# DarkPill_V1_1_eagle_V7_6.net
KiCad netlist of a schematic drawn in EAGLE
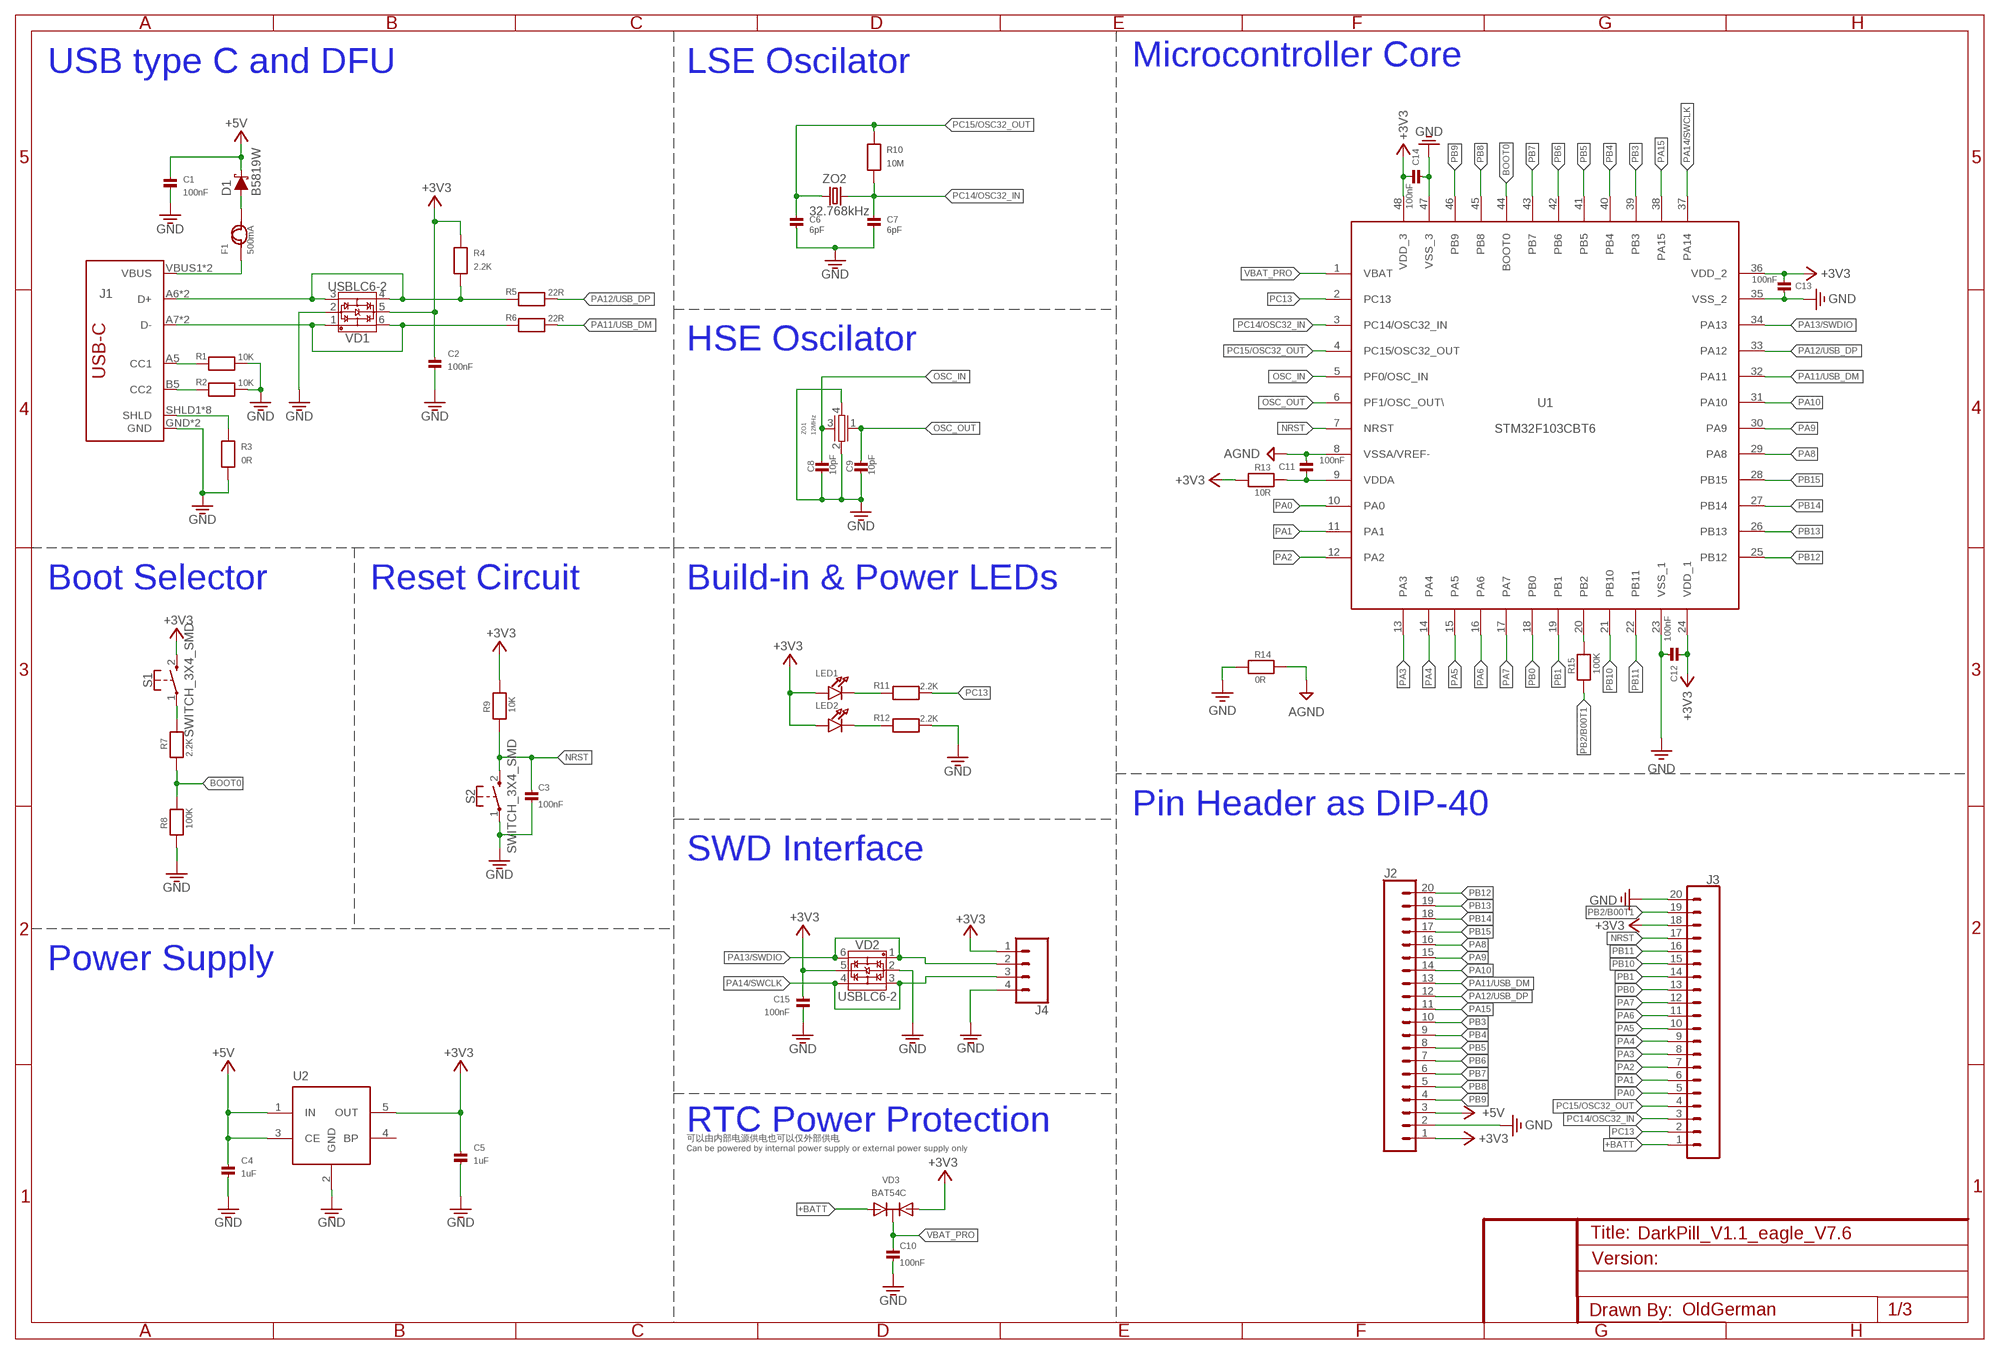
[diagram p0: schematic, sheet 1]

(export (version "E")
  (design (tool "Eeschema 10.0.6"))
  (components
    (comp (ref "C1")
      (value "100nF")
      (footprint "eagle-import:0603")
      (libsource (lib "eagle-import") (part "CAP_CERAMIC0603"))
    )
    (comp (ref "C2")
      (value "100nF")
      (footprint "eagle-import:0603")
      (libsource (lib "eagle-import") (part "CAP_CERAMIC0603"))
    )
    (comp (ref "C3")
      (value "100nF")
      (footprint "eagle-import:0603")
      (libsource (lib "eagle-import") (part "CAP_CERAMIC0603"))
    )
    (comp (ref "C4")
      (value "1uF")
      (footprint "eagle-import:0603")
      (libsource (lib "eagle-import") (part "CAP_CERAMIC0603"))
    )
    (comp (ref "C5")
      (value "1uF")
      (footprint "eagle-import:0603")
      (libsource (lib "eagle-import") (part "CAP_CERAMIC0603"))
    )
    (comp (ref "C6")
      (value "6pF")
      (footprint "eagle-import:0603")
      (libsource (lib "eagle-import") (part "CAP_CERAMIC0603"))
    )
    (comp (ref "C7")
      (value "6pF")
      (footprint "eagle-import:0603")
      (libsource (lib "eagle-import") (part "CAP_CERAMIC0603"))
    )
    (comp (ref "C8")
      (value "10pF")
      (footprint "eagle-import:0603")
      (libsource (lib "eagle-import") (part "CAP_CERAMIC0603"))
    )
    (comp (ref "C9")
      (value "10pF")
      (footprint "eagle-import:0603")
      (libsource (lib "eagle-import") (part "CAP_CERAMIC0603"))
    )
    (comp (ref "C10")
      (value "100nF")
      (footprint "eagle-import:0603")
      (libsource (lib "eagle-import") (part "CAP_CERAMIC0603"))
    )
    (comp (ref "C11")
      (value "100nF")
      (footprint "eagle-import:0603")
      (libsource (lib "eagle-import") (part "CAP_CERAMIC0603"))
    )
    (comp (ref "C12")
      (value "100nF")
      (footprint "eagle-import:0603")
      (libsource (lib "eagle-import") (part "CAP_CERAMIC0603"))
    )
    (comp (ref "C13")
      (value "100nF")
      (footprint "eagle-import:0603")
      (libsource (lib "eagle-import") (part "CAP_CERAMIC0603"))
    )
    (comp (ref "C14")
      (value "100nF")
      (footprint "eagle-import:0603")
      (libsource (lib "eagle-import") (part "CAP_CERAMIC0603"))
    )
    (comp (ref "C15")
      (value "100nF")
      (footprint "eagle-import:0603")
      (libsource (lib "eagle-import") (part "CAP_CERAMIC0603"))
    )
    (comp (ref "D1")
      (value "B5819W")
      (footprint "eagle-import:SOD-323")
      (libsource (lib "eagle-import") (part "B5819W-SOD323"))
    )
    (comp (ref "F1")
      (value "500mA")
      (footprint "eagle-import:0603")
      (libsource (lib "eagle-import") (part "FUSE"))
    )
    (comp (ref "J1")
      (value "USB_C2-LAYER")
      (footprint "eagle-import:USB-C-16P")
      (libsource (lib "eagle-import") (part "USB_C2-LAYER"))
    )
    (comp (ref "J2")
      (value "CONN_20")
      (footprint "eagle-import:1X20")
      (libsource (lib "eagle-import") (part "CONN_20"))
    )
    (comp (ref "J3")
      (value "CONN_20")
      (footprint "eagle-import:1X20")
      (libsource (lib "eagle-import") (part "CONN_20"))
    )
    (comp (ref "J4")
      (value "CONN_04PTH")
      (footprint "eagle-import:1X04")
      (libsource (lib "eagle-import") (part "CONN_04PTH"))
    )
    (comp (ref "LED1")
      (value "LED_0603_MICRO")
      (footprint "eagle-import:0603_LED")
      (libsource (lib "eagle-import") (part "LED_0603_MICRO"))
    )
    (comp (ref "LED2")
      (value "LED_0603_MICRO")
      (footprint "eagle-import:0603_LED")
      (libsource (lib "eagle-import") (part "LED_0603_MICRO"))
    )
    (comp (ref "R1")
      (value "10K")
      (footprint "eagle-import:0603")
      (libsource (lib "eagle-import") (part "RESISTOR0603"))
    )
    (comp (ref "R2")
      (value "10K")
      (footprint "eagle-import:0603")
      (libsource (lib "eagle-import") (part "RESISTOR0603"))
    )
    (comp (ref "R3")
      (value "0R")
      (footprint "eagle-import:0603")
      (libsource (lib "eagle-import") (part "RESISTOR0603"))
    )
    (comp (ref "R4")
      (value "2.2K")
      (footprint "eagle-import:0603")
      (libsource (lib "eagle-import") (part "RESISTOR0603"))
    )
    (comp (ref "R5")
      (value "22R")
      (footprint "eagle-import:0603")
      (libsource (lib "eagle-import") (part "RESISTOR0603"))
    )
    (comp (ref "R6")
      (value "22R")
      (footprint "eagle-import:0603")
      (libsource (lib "eagle-import") (part "RESISTOR0603"))
    )
    (comp (ref "R7")
      (value "2.2K")
      (footprint "eagle-import:0603")
      (libsource (lib "eagle-import") (part "RESISTOR0603"))
    )
    (comp (ref "R8")
      (value "100K")
      (footprint "eagle-import:0603")
      (libsource (lib "eagle-import") (part "RESISTOR0603"))
    )
    (comp (ref "R9")
      (value "10K")
      (footprint "eagle-import:0603")
      (libsource (lib "eagle-import") (part "RESISTOR0603"))
    )
    (comp (ref "R10")
      (value "10M")
      (footprint "eagle-import:0603")
      (libsource (lib "eagle-import") (part "RESISTOR0603"))
    )
    (comp (ref "R11")
      (value "2.2K")
      (footprint "eagle-import:0603")
      (libsource (lib "eagle-import") (part "RESISTOR0603"))
    )
    (comp (ref "R12")
      (value "2.2K")
      (footprint "eagle-import:0603")
      (libsource (lib "eagle-import") (part "RESISTOR0603"))
    )
    (comp (ref "R13")
      (value "10R")
      (footprint "eagle-import:0603")
      (libsource (lib "eagle-import") (part "RESISTOR0603"))
    )
    (comp (ref "R14")
      (value "0R")
      (footprint "eagle-import:0603")
      (libsource (lib "eagle-import") (part "RESISTOR0603"))
    )
    (comp (ref "R15")
      (value "100K")
      (footprint "eagle-import:0603")
      (libsource (lib "eagle-import") (part "RESISTOR0603"))
    )
    (comp (ref "S1")
      (value "SWITCH_3X4_SMD")
      (footprint "eagle-import:SWITCH_3X4_SMD")
      (libsource (lib "eagle-import") (part "SWITCH_3X4_SMD"))
    )
    (comp (ref "S2")
      (value "SWITCH_3X4_SMD")
      (footprint "eagle-import:SWITCH_3X4_SMD")
      (libsource (lib "eagle-import") (part "SWITCH_3X4_SMD"))
    )
    (comp (ref "U1")
      (value "STM32F103CBT6")
      (footprint "eagle-import:TQFP48")
      (libsource (lib "eagle-import") (part "STM32F303CBT6"))
    )
    (comp (ref "U2")
      (value "ME6211C33M5G-N")
      (footprint "eagle-import:SOT23-5")
      (libsource (lib "eagle-import") (part "ME6211C33M5G-N"))
    )
    (comp (ref "VD1")
      (value "USBLC6-2")
      (footprint "eagle-import:SOT23-6")
      (libsource (lib "eagle-import") (part "USBLC6-2SOT23-6"))
    )
    (comp (ref "VD2")
      (value "USBLC6-2")
      (footprint "eagle-import:SOT23-6")
      (libsource (lib "eagle-import") (part "USBLC6-2SOT23-6"))
    )
    (comp (ref "VD3")
      (value "BAT54C")
      (footprint "eagle-import:SOT23-R")
      (libsource (lib "eagle-import") (part "BAT54C"))
    )
    (comp (ref "ZO1")
      (value "12MHz")
      (footprint "eagle-import:3.2X2.5_KX-7")
      (libsource (lib "eagle-import") (part "3225_CRYSTALL"))
    )
    (comp (ref "ZO2")
      (value "32.768kHz")
      (footprint "eagle-import:3.2X1.5")
      (libsource (lib "eagle-import") (part "KX-327-NHF"))
    )
  )
  (nets
    (net (code "1") (name "+3V3") (class "Default")
      (node (ref "C12") (pin "2") (pinfunction "P$2_2") (pintype "passive"))
      (node (ref "C13") (pin "2") (pinfunction "P$2_2") (pintype "passive"))
      (node (ref "C14") (pin "2") (pinfunction "P$2_2") (pintype "passive"))
      (node (ref "C15") (pin "1") (pinfunction "P$1_1") (pintype "passive"))
      (node (ref "C2") (pin "1") (pinfunction "P$1_1") (pintype "passive"))
      (node (ref "C5") (pin "1") (pinfunction "P$1_1") (pintype "passive"))
      (node (ref "J2") (pin "1") (pinfunction "1_1") (pintype "passive"))
      (node (ref "J3") (pin "18") (pinfunction "18_18") (pintype "passive"))
      (node (ref "J4") (pin "1") (pinfunction "1_1") (pintype "passive"))
      (node (ref "LED1") (pin "1") (pinfunction "A_1") (pintype "passive"))
      (node (ref "LED2") (pin "1") (pinfunction "A_1") (pintype "passive"))
      (node (ref "R13") (pin "2") (pinfunction "2_2") (pintype "passive"))
      (node (ref "R4") (pin "2") (pinfunction "2_2") (pintype "passive"))
      (node (ref "R9") (pin "1") (pinfunction "1_1") (pintype "passive"))
      (node (ref "S1") (pin "2") (pinfunction "2_2") (pintype "passive"))
      (node (ref "U1") (pin "24") (pinfunction "VDD_1_24") (pintype "bidirectional"))
      (node (ref "U1") (pin "36") (pinfunction "VDD_2_36") (pintype "bidirectional"))
      (node (ref "U1") (pin "48") (pinfunction "VDD_3_48") (pintype "bidirectional"))
      (node (ref "U2") (pin "5") (pinfunction "OUT_5") (pintype "bidirectional"))
      (node (ref "VD1") (pin "5") (pinfunction "P$5_5") (pintype "bidirectional"))
      (node (ref "VD2") (pin "5") (pinfunction "P$5_5") (pintype "bidirectional"))
      (node (ref "VD3") (pin "1") (pinfunction "A1_1") (pintype "passive"))
    )
    (net (code "2") (name "+5V") (class "Default")
      (node (ref "C1") (pin "1") (pinfunction "P$1_1") (pintype "passive"))
      (node (ref "C4") (pin "1") (pinfunction "P$1_1") (pintype "passive"))
      (node (ref "D1") (pin "C") (pinfunction "C_C") (pintype "passive"))
      (node (ref "J2") (pin "3") (pinfunction "3_3") (pintype "passive"))
      (node (ref "U2") (pin "1") (pinfunction "IN_1") (pintype "bidirectional"))
      (node (ref "U2") (pin "3") (pinfunction "CE_3") (pintype "bidirectional"))
    )
    (net (code "3") (name "+BATT") (class "Default")
      (node (ref "J3") (pin "1") (pinfunction "1_1") (pintype "passive"))
      (node (ref "VD3") (pin "2") (pinfunction "A2_2") (pintype "passive"))
    )
    (net (code "4") (name "AGND") (class "Default")
      (node (ref "C11") (pin "1") (pinfunction "P$1_1") (pintype "passive"))
      (node (ref "R14") (pin "1") (pinfunction "1_1") (pintype "passive"))
      (node (ref "U1") (pin "8") (pinfunction "VSSA/VREF-_8") (pintype "bidirectional"))
    )
    (net (code "5") (name "BOOT0") (class "Default")
      (node (ref "R7") (pin "1") (pinfunction "1_1") (pintype "passive"))
      (node (ref "R8") (pin "1") (pinfunction "1_1") (pintype "passive"))
      (node (ref "U1") (pin "44") (pinfunction "BOOT0_44") (pintype "bidirectional"))
    )
    (net (code "6") (name "GND") (class "Default")
      (node (ref "C1") (pin "2") (pinfunction "P$2_2") (pintype "passive"))
      (node (ref "C10") (pin "2") (pinfunction "P$2_2") (pintype "passive"))
      (node (ref "C12") (pin "1") (pinfunction "P$1_1") (pintype "passive"))
      (node (ref "C13") (pin "1") (pinfunction "P$1_1") (pintype "passive"))
      (node (ref "C14") (pin "1") (pinfunction "P$1_1") (pintype "passive"))
      (node (ref "C15") (pin "2") (pinfunction "P$2_2") (pintype "passive"))
      (node (ref "C2") (pin "2") (pinfunction "P$2_2") (pintype "passive"))
      (node (ref "C3") (pin "2") (pinfunction "P$2_2") (pintype "passive"))
      (node (ref "C4") (pin "2") (pinfunction "P$2_2") (pintype "passive"))
      (node (ref "C5") (pin "2") (pinfunction "P$2_2") (pintype "passive"))
      (node (ref "C6") (pin "1") (pinfunction "P$1_1") (pintype "passive"))
      (node (ref "C7") (pin "1") (pinfunction "P$1_1") (pintype "passive"))
      (node (ref "C8") (pin "1") (pinfunction "P$1_1") (pintype "passive"))
      (node (ref "C9") (pin "1") (pinfunction "P$1_1") (pintype "passive"))
      (node (ref "J1") (pin "GND") (pinfunction "GND_GND") (pintype "bidirectional"))
      (node (ref "J1") (pin "GND2") (pinfunction "GND_GND2") (pintype "bidirectional"))
      (node (ref "J2") (pin "2") (pinfunction "2_2") (pintype "passive"))
      (node (ref "J3") (pin "20") (pinfunction "20_20") (pintype "passive"))
      (node (ref "J4") (pin "4") (pinfunction "4_4") (pintype "passive"))
      (node (ref "R1") (pin "2") (pinfunction "2_2") (pintype "passive"))
      (node (ref "R12") (pin "2") (pinfunction "2_2") (pintype "passive"))
      (node (ref "R14") (pin "2") (pinfunction "2_2") (pintype "passive"))
      (node (ref "R2") (pin "2") (pinfunction "2_2") (pintype "passive"))
      (node (ref "R3") (pin "1") (pinfunction "1_1") (pintype "passive"))
      (node (ref "R8") (pin "2") (pinfunction "2_2") (pintype "passive"))
      (node (ref "S2") (pin "1") (pinfunction "1_1") (pintype "passive"))
      (node (ref "U1") (pin "23") (pinfunction "VSS_1_23") (pintype "bidirectional"))
      (node (ref "U1") (pin "35") (pinfunction "VSS_2_35") (pintype "bidirectional"))
      (node (ref "U1") (pin "47") (pinfunction "VSS_3_47") (pintype "bidirectional"))
      (node (ref "U2") (pin "2") (pinfunction "GND_2") (pintype "bidirectional"))
      (node (ref "VD1") (pin "2") (pinfunction "P$2_2") (pintype "bidirectional"))
      (node (ref "VD2") (pin "2") (pinfunction "P$2_2") (pintype "bidirectional"))
      (node (ref "ZO1") (pin "2") (pinfunction "P$3_2") (pintype "power_in"))
      (node (ref "ZO1") (pin "4") (pinfunction "P$4_4") (pintype "power_in"))
    )
    (net (code "7") (name "NRST") (class "Default")
      (node (ref "C3") (pin "1") (pinfunction "P$1_1") (pintype "passive"))
      (node (ref "J3") (pin "17") (pinfunction "17_17") (pintype "passive"))
      (node (ref "R9") (pin "2") (pinfunction "2_2") (pintype "passive"))
      (node (ref "S2") (pin "2") (pinfunction "2_2") (pintype "passive"))
      (node (ref "U1") (pin "7") (pinfunction "NRST_7") (pintype "bidirectional"))
    )
    (net (code "8") (name "Net-(C11-P$2)") (class "Default")
      (node (ref "C11") (pin "2") (pinfunction "P$2_2") (pintype "passive"))
      (node (ref "R13") (pin "1") (pinfunction "1_1") (pintype "passive"))
      (node (ref "U1") (pin "9") (pinfunction "VDDA_9") (pintype "bidirectional"))
    )
    (net (code "9") (name "Net-(D1-PadA)") (class "Default")
      (node (ref "D1") (pin "A") (pinfunction "A_A") (pintype "passive"))
      (node (ref "F1") (pin "2") (pinfunction "2_2") (pintype "bidirectional"))
    )
    (net (code "10") (name "Net-(F1-Pad1)") (class "Default")
      (node (ref "F1") (pin "1") (pinfunction "1_1") (pintype "bidirectional"))
      (node (ref "J1") (pin "VBUS1") (pinfunction "VBUS_VBUS1") (pintype "bidirectional"))
      (node (ref "J1") (pin "VBUS2") (pinfunction "VBUS_VBUS2") (pintype "bidirectional"))
    )
    (net (code "11") (name "Net-(J1-CC1)") (class "Default")
      (node (ref "J1") (pin "A5") (pinfunction "CC1_A5") (pintype "bidirectional"))
      (node (ref "R1") (pin "1") (pinfunction "1_1") (pintype "passive"))
    )
    (net (code "12") (name "Net-(J1-CC2)") (class "Default")
      (node (ref "J1") (pin "B5") (pinfunction "CC2_B5") (pintype "bidirectional"))
      (node (ref "R2") (pin "1") (pinfunction "1_1") (pintype "passive"))
    )
    (net (code "13") (name "Net-(J1-SHLD-PadSHLD1)") (class "Default")
      (node (ref "J1") (pin "SHLD1") (pinfunction "SHLD_SHLD1") (pintype "bidirectional"))
      (node (ref "J1") (pin "SHLD2") (pinfunction "SHLD_SHLD2") (pintype "bidirectional"))
      (node (ref "J1") (pin "SHLD3") (pinfunction "SHLD_SHLD3") (pintype "bidirectional"))
      (node (ref "J1") (pin "SHLD4") (pinfunction "SHLD_SHLD4") (pintype "bidirectional"))
      (node (ref "J1") (pin "SHLD5") (pinfunction "SHLD_SHLD5") (pintype "bidirectional"))
      (node (ref "J1") (pin "SHLD6") (pinfunction "SHLD_SHLD6") (pintype "bidirectional"))
      (node (ref "J1") (pin "SHLD7") (pinfunction "SHLD_SHLD7") (pintype "bidirectional"))
      (node (ref "J1") (pin "SHLD8") (pinfunction "SHLD_SHLD8") (pintype "bidirectional"))
      (node (ref "R3") (pin "2") (pinfunction "2_2") (pintype "passive"))
    )
    (net (code "14") (name "Net-(LED1-C)") (class "Default")
      (node (ref "LED1") (pin "2") (pinfunction "C_2") (pintype "passive"))
      (node (ref "R11") (pin "1") (pinfunction "1_1") (pintype "passive"))
    )
    (net (code "15") (name "Net-(LED2-C)") (class "Default")
      (node (ref "LED2") (pin "2") (pinfunction "C_2") (pintype "passive"))
      (node (ref "R12") (pin "1") (pinfunction "1_1") (pintype "passive"))
    )
    (net (code "16") (name "Net-(R7-Pad2)") (class "Default")
      (node (ref "R7") (pin "2") (pinfunction "2_2") (pintype "passive"))
      (node (ref "S1") (pin "1") (pinfunction "1_1") (pintype "passive"))
    )
    (net (code "17") (name "Net-(U1-PB2)") (class "Default")
      (node (ref "R15") (pin "1") (pinfunction "1_1") (pintype "passive"))
      (node (ref "U1") (pin "20") (pinfunction "PB2_20") (pintype "bidirectional"))
    )
    (net (code "18") (name "Net-(VD1-P$1)") (class "Default")
      (node (ref "J1") (pin "A7") (pinfunction "D-_A7") (pintype "bidirectional"))
      (node (ref "J1") (pin "B7") (pinfunction "D-_B7") (pintype "bidirectional"))
      (node (ref "R6") (pin "1") (pinfunction "1_1") (pintype "passive"))
      (node (ref "VD1") (pin "1") (pinfunction "P$1_1") (pintype "bidirectional"))
      (node (ref "VD1") (pin "6") (pinfunction "P$6_6") (pintype "bidirectional"))
    )
    (net (code "19") (name "Net-(VD1-P$3)") (class "Default")
      (node (ref "J1") (pin "A6") (pinfunction "D+_A6") (pintype "bidirectional"))
      (node (ref "J1") (pin "B6") (pinfunction "D+_B6") (pintype "bidirectional"))
      (node (ref "R4") (pin "1") (pinfunction "1_1") (pintype "passive"))
      (node (ref "R5") (pin "1") (pinfunction "1_1") (pintype "passive"))
      (node (ref "VD1") (pin "3") (pinfunction "P$3_3") (pintype "bidirectional"))
      (node (ref "VD1") (pin "4") (pinfunction "P$4_4") (pintype "bidirectional"))
    )
    (net (code "20") (name "OSC_IN") (class "Default")
      (node (ref "C8") (pin "2") (pinfunction "P$2_2") (pintype "passive"))
      (node (ref "U1") (pin "5") (pinfunction "PF0/OSC_IN_5") (pintype "bidirectional"))
      (node (ref "ZO1") (pin "3") (pinfunction "P$2_3") (pintype "bidirectional"))
    )
    (net (code "21") (name "OSC_OUT") (class "Default")
      (node (ref "C9") (pin "2") (pinfunction "P$2_2") (pintype "passive"))
      (node (ref "U1") (pin "6") (pinfunction "PF1/OSC_OUT\\_6") (pintype "bidirectional"))
      (node (ref "ZO1") (pin "1") (pinfunction "P$1_1") (pintype "bidirectional"))
    )
    (net (code "22") (name "PA0") (class "Default")
      (node (ref "J3") (pin "5") (pinfunction "5_5") (pintype "passive"))
      (node (ref "U1") (pin "10") (pinfunction "PA0_10") (pintype "bidirectional"))
    )
    (net (code "23") (name "PA1") (class "Default")
      (node (ref "J3") (pin "6") (pinfunction "6_6") (pintype "passive"))
      (node (ref "U1") (pin "11") (pinfunction "PA1_11") (pintype "bidirectional"))
    )
    (net (code "24") (name "PA2") (class "Default")
      (node (ref "J3") (pin "7") (pinfunction "7_7") (pintype "passive"))
      (node (ref "U1") (pin "12") (pinfunction "PA2_12") (pintype "bidirectional"))
    )
    (net (code "25") (name "PA3") (class "Default")
      (node (ref "J3") (pin "8") (pinfunction "8_8") (pintype "passive"))
      (node (ref "U1") (pin "13") (pinfunction "PA3_13") (pintype "bidirectional"))
    )
    (net (code "26") (name "PA4") (class "Default")
      (node (ref "J3") (pin "9") (pinfunction "9_9") (pintype "passive"))
      (node (ref "U1") (pin "14") (pinfunction "PA4_14") (pintype "bidirectional"))
    )
    (net (code "27") (name "PA5") (class "Default")
      (node (ref "J3") (pin "10") (pinfunction "10_10") (pintype "passive"))
      (node (ref "U1") (pin "15") (pinfunction "PA5_15") (pintype "bidirectional"))
    )
    (net (code "28") (name "PA6") (class "Default")
      (node (ref "J3") (pin "11") (pinfunction "11_11") (pintype "passive"))
      (node (ref "U1") (pin "16") (pinfunction "PA6_16") (pintype "bidirectional"))
    )
    (net (code "29") (name "PA7") (class "Default")
      (node (ref "J3") (pin "12") (pinfunction "12_12") (pintype "passive"))
      (node (ref "U1") (pin "17") (pinfunction "PA7_17") (pintype "bidirectional"))
    )
    (net (code "30") (name "PA8") (class "Default")
      (node (ref "J2") (pin "16") (pinfunction "16_16") (pintype "passive"))
      (node (ref "U1") (pin "29") (pinfunction "PA8_29") (pintype "bidirectional"))
    )
    (net (code "31") (name "PA9") (class "Default")
      (node (ref "J2") (pin "15") (pinfunction "15_15") (pintype "passive"))
      (node (ref "U1") (pin "30") (pinfunction "PA9_30") (pintype "bidirectional"))
    )
    (net (code "32") (name "PA10") (class "Default")
      (node (ref "J2") (pin "14") (pinfunction "14_14") (pintype "passive"))
      (node (ref "U1") (pin "31") (pinfunction "PA10_31") (pintype "bidirectional"))
    )
    (net (code "33") (name "PA11{slash}USB_DM") (class "Default")
      (node (ref "J2") (pin "13") (pinfunction "13_13") (pintype "passive"))
      (node (ref "R6") (pin "2") (pinfunction "2_2") (pintype "passive"))
      (node (ref "U1") (pin "32") (pinfunction "PA11_32") (pintype "bidirectional"))
    )
    (net (code "34") (name "PA12{slash}USB_DP") (class "Default")
      (node (ref "J2") (pin "12") (pinfunction "12_12") (pintype "passive"))
      (node (ref "R5") (pin "2") (pinfunction "2_2") (pintype "passive"))
      (node (ref "U1") (pin "33") (pinfunction "PA12_33") (pintype "bidirectional"))
    )
    (net (code "35") (name "PA13{slash}SWDIO") (class "Default")
      (node (ref "J4") (pin "2") (pinfunction "2_2") (pintype "passive"))
      (node (ref "U1") (pin "34") (pinfunction "PA13_34") (pintype "bidirectional"))
      (node (ref "VD2") (pin "1") (pinfunction "P$1_1") (pintype "bidirectional"))
      (node (ref "VD2") (pin "6") (pinfunction "P$6_6") (pintype "bidirectional"))
    )
    (net (code "36") (name "PA14{slash}SWCLK") (class "Default")
      (node (ref "J4") (pin "3") (pinfunction "3_3") (pintype "passive"))
      (node (ref "U1") (pin "37") (pinfunction "PA14_37") (pintype "bidirectional"))
      (node (ref "VD2") (pin "3") (pinfunction "P$3_3") (pintype "bidirectional"))
      (node (ref "VD2") (pin "4") (pinfunction "P$4_4") (pintype "bidirectional"))
    )
    (net (code "37") (name "PA15") (class "Default")
      (node (ref "J2") (pin "11") (pinfunction "11_11") (pintype "passive"))
      (node (ref "U1") (pin "38") (pinfunction "PA15_38") (pintype "bidirectional"))
    )
    (net (code "38") (name "PB0") (class "Default")
      (node (ref "J3") (pin "13") (pinfunction "13_13") (pintype "passive"))
      (node (ref "U1") (pin "18") (pinfunction "PB0_18") (pintype "bidirectional"))
    )
    (net (code "39") (name "PB1") (class "Default")
      (node (ref "J3") (pin "14") (pinfunction "14_14") (pintype "passive"))
      (node (ref "U1") (pin "19") (pinfunction "PB1_19") (pintype "bidirectional"))
    )
    (net (code "40") (name "PB2{slash}B00T1") (class "Default")
      (node (ref "J3") (pin "19") (pinfunction "19_19") (pintype "passive"))
      (node (ref "R15") (pin "2") (pinfunction "2_2") (pintype "passive"))
    )
    (net (code "41") (name "PB3") (class "Default")
      (node (ref "J2") (pin "10") (pinfunction "10_10") (pintype "passive"))
      (node (ref "U1") (pin "39") (pinfunction "PB3_39") (pintype "bidirectional"))
    )
    (net (code "42") (name "PB4") (class "Default")
      (node (ref "J2") (pin "9") (pinfunction "9_9") (pintype "passive"))
      (node (ref "U1") (pin "40") (pinfunction "PB4_40") (pintype "bidirectional"))
    )
    (net (code "43") (name "PB5") (class "Default")
      (node (ref "J2") (pin "8") (pinfunction "8_8") (pintype "passive"))
      (node (ref "U1") (pin "41") (pinfunction "PB5_41") (pintype "bidirectional"))
    )
    (net (code "44") (name "PB6") (class "Default")
      (node (ref "J2") (pin "7") (pinfunction "7_7") (pintype "passive"))
      (node (ref "U1") (pin "42") (pinfunction "PB6_42") (pintype "bidirectional"))
    )
    (net (code "45") (name "PB7") (class "Default")
      (node (ref "J2") (pin "6") (pinfunction "6_6") (pintype "passive"))
      (node (ref "U1") (pin "43") (pinfunction "PB7_43") (pintype "bidirectional"))
    )
    (net (code "46") (name "PB8") (class "Default")
      (node (ref "J2") (pin "5") (pinfunction "5_5") (pintype "passive"))
      (node (ref "U1") (pin "45") (pinfunction "PB8_45") (pintype "bidirectional"))
    )
    (net (code "47") (name "PB9") (class "Default")
      (node (ref "J2") (pin "4") (pinfunction "4_4") (pintype "passive"))
      (node (ref "U1") (pin "46") (pinfunction "PB9_46") (pintype "bidirectional"))
    )
    (net (code "48") (name "PB10") (class "Default")
      (node (ref "J3") (pin "15") (pinfunction "15_15") (pintype "passive"))
      (node (ref "U1") (pin "21") (pinfunction "PB10_21") (pintype "bidirectional"))
    )
    (net (code "49") (name "PB11") (class "Default")
      (node (ref "J3") (pin "16") (pinfunction "16_16") (pintype "passive"))
      (node (ref "U1") (pin "22") (pinfunction "PB11_22") (pintype "bidirectional"))
    )
    (net (code "50") (name "PB12") (class "Default")
      (node (ref "J2") (pin "20") (pinfunction "20_20") (pintype "passive"))
      (node (ref "U1") (pin "25") (pinfunction "PB12_25") (pintype "bidirectional"))
    )
    (net (code "51") (name "PB13") (class "Default")
      (node (ref "J2") (pin "19") (pinfunction "19_19") (pintype "passive"))
      (node (ref "U1") (pin "26") (pinfunction "PB13_26") (pintype "bidirectional"))
    )
    (net (code "52") (name "PB14") (class "Default")
      (node (ref "J2") (pin "18") (pinfunction "18_18") (pintype "passive"))
      (node (ref "U1") (pin "27") (pinfunction "PB14_27") (pintype "bidirectional"))
    )
    (net (code "53") (name "PB15") (class "Default")
      (node (ref "J2") (pin "17") (pinfunction "17_17") (pintype "passive"))
      (node (ref "U1") (pin "28") (pinfunction "PB15_28") (pintype "bidirectional"))
    )
    (net (code "54") (name "PC13") (class "Default")
      (node (ref "J3") (pin "2") (pinfunction "2_2") (pintype "passive"))
      (node (ref "R11") (pin "2") (pinfunction "2_2") (pintype "passive"))
      (node (ref "U1") (pin "2") (pinfunction "PC13_2") (pintype "bidirectional"))
    )
    (net (code "55") (name "PC14{slash}OSC32_IN") (class "Default")
      (node (ref "C7") (pin "2") (pinfunction "P$2_2") (pintype "passive"))
      (node (ref "J3") (pin "3") (pinfunction "3_3") (pintype "passive"))
      (node (ref "R10") (pin "2") (pinfunction "2_2") (pintype "passive"))
      (node (ref "U1") (pin "3") (pinfunction "PC14/OSC32_IN_3") (pintype "bidirectional"))
      (node (ref "ZO2") (pin "2") (pinfunction "2_2") (pintype "passive"))
    )
    (net (code "56") (name "PC15{slash}OSC32_OUT") (class "Default")
      (node (ref "C6") (pin "2") (pinfunction "P$2_2") (pintype "passive"))
      (node (ref "J3") (pin "4") (pinfunction "4_4") (pintype "passive"))
      (node (ref "R10") (pin "1") (pinfunction "1_1") (pintype "passive"))
      (node (ref "U1") (pin "4") (pinfunction "PC15/OSC32_OUT_4") (pintype "bidirectional"))
      (node (ref "ZO2") (pin "1") (pinfunction "1_1") (pintype "passive"))
    )
    (net (code "57") (name "VBAT_PRO") (class "Default")
      (node (ref "C10") (pin "1") (pinfunction "P$1_1") (pintype "passive"))
      (node (ref "U1") (pin "1") (pinfunction "VBAT_1") (pintype "bidirectional"))
      (node (ref "VD3") (pin "3") (pinfunction "C_3") (pintype "passive"))
    )
    (net (code "58") (name "unconnected-(U2-BP-Pad4)") (class "Default")
      (node (ref "U2") (pin "4") (pinfunction "BP_4") (pintype "bidirectional"))
    )
  )
)
